# ITL230216.net
KiCad netlist of a schematic drawn in Altium Designer
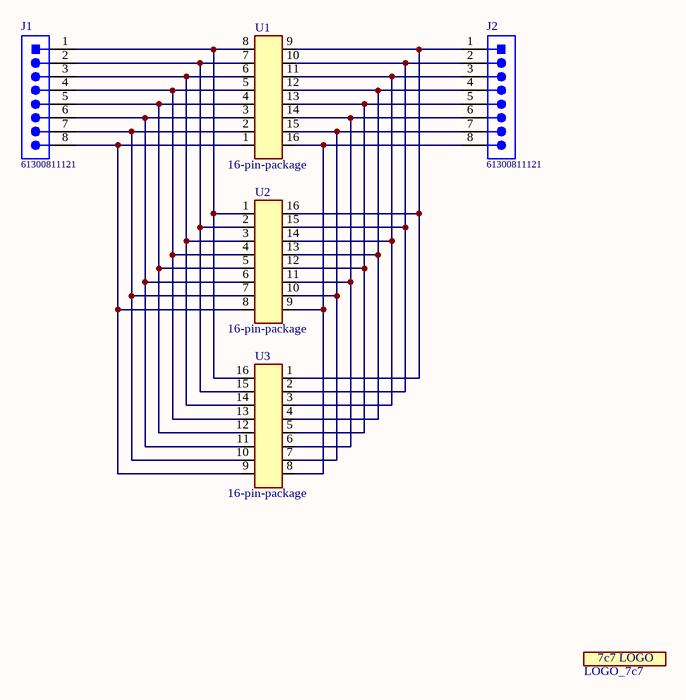
[diagram p0: ITL230216.SchDoc]

(export (version "E")
  (design (tool "Eeschema 10.0.6"))
  (components
    (comp (ref "GR1")
      (value "LOGO_7c7")
      (footprint "LOGO_7c7_silk_3MM")
      (description "The 7c7 logo: Be proud of our designs and stamp that logo on there!")
      (libsource (lib "7c7 Engineering") (part "LOGO_7c7-Symbol-1"))
    )
    (comp (ref "J1")
      (value "61300811121")
      (footprint "61300811121")
      (description "WR-PHD Pin Header, THT, pitch 2.54mm, Single Row, Vertical, 8p")
      (fields (field (name "MANUFACTURER") "Wurth Elektronik"))
      (libsource (lib "") (part "HDR8_1"))
    )
    (comp (ref "J2")
      (value "61300811121")
      (footprint "61300811121")
      (description "WR-PHD Pin Header, THT, pitch 2.54mm, Single Row, Vertical, 8p")
      (fields (field (name "MANUFACTURER") "Wurth Elektronik"))
      (libsource (lib "7c7 Engineering") (part "HDR8"))
    )
    (comp (ref "U1")
      (value "16-pin-package")
      (footprint "TSSOP16-0.65-4.4-L")
      (description "package adapter")
      (libsource (lib "7c7 Engineering") (part "16 pin device"))
    )
    (comp (ref "U2")
      (value "16-pin-package")
      (footprint "SOP16-N")
      (description "package adapter")
      (libsource (lib "") (part "16 pin device_1"))
    )
    (comp (ref "U3")
      (value "16-pin-package")
      (footprint "MSOP16")
      (description "package adapter")
      (libsource (lib "") (part "16 pin device_2"))
    )
  )
  (nets
    (net (code "1") (name "Net-(J1-Pad1)") (class "Default")
      (node (ref "J1") (pin "1") (pinfunction "1_1") (pintype "passive"))
      (node (ref "U1") (pin "8") (pinfunction "8_8") (pintype "power_in"))
      (node (ref "U2") (pin "1") (pinfunction "1_1") (pintype "power_in"))
      (node (ref "U3") (pin "16") (pinfunction "16_16") (pintype "power_in"))
    )
    (net (code "2") (name "Net-(J1-Pad2)") (class "Default")
      (node (ref "J1") (pin "2") (pinfunction "2_2") (pintype "passive"))
      (node (ref "U1") (pin "7") (pinfunction "7_7") (pintype "power_in"))
      (node (ref "U2") (pin "2") (pinfunction "2_2") (pintype "power_in"))
      (node (ref "U3") (pin "15") (pinfunction "15_15") (pintype "power_in"))
    )
    (net (code "3") (name "Net-(J1-Pad3)") (class "Default")
      (node (ref "J1") (pin "3") (pinfunction "3_3") (pintype "passive"))
      (node (ref "U1") (pin "6") (pinfunction "6_6") (pintype "power_in"))
      (node (ref "U2") (pin "3") (pinfunction "3_3") (pintype "power_in"))
      (node (ref "U3") (pin "14") (pinfunction "14_14") (pintype "power_in"))
    )
    (net (code "4") (name "Net-(J1-Pad4)") (class "Default")
      (node (ref "J1") (pin "4") (pinfunction "4_4") (pintype "passive"))
      (node (ref "U1") (pin "5") (pinfunction "5_5") (pintype "power_in"))
      (node (ref "U2") (pin "4") (pinfunction "4_4") (pintype "power_in"))
      (node (ref "U3") (pin "13") (pinfunction "13_13") (pintype "power_in"))
    )
    (net (code "5") (name "Net-(J1-Pad5)") (class "Default")
      (node (ref "J1") (pin "5") (pinfunction "5_5") (pintype "passive"))
      (node (ref "U1") (pin "4") (pinfunction "4_4") (pintype "power_in"))
      (node (ref "U2") (pin "5") (pinfunction "5_5") (pintype "power_in"))
      (node (ref "U3") (pin "12") (pinfunction "12_12") (pintype "power_in"))
    )
    (net (code "6") (name "Net-(J1-Pad6)") (class "Default")
      (node (ref "J1") (pin "6") (pinfunction "6_6") (pintype "passive"))
      (node (ref "U1") (pin "3") (pinfunction "3_3") (pintype "power_in"))
      (node (ref "U2") (pin "6") (pinfunction "6_6") (pintype "power_in"))
      (node (ref "U3") (pin "11") (pinfunction "11_11") (pintype "power_in"))
    )
    (net (code "7") (name "Net-(J1-Pad7)") (class "Default")
      (node (ref "J1") (pin "7") (pinfunction "7_7") (pintype "passive"))
      (node (ref "U1") (pin "2") (pinfunction "2_2") (pintype "power_in"))
      (node (ref "U2") (pin "7") (pinfunction "7_7") (pintype "power_in"))
      (node (ref "U3") (pin "10") (pinfunction "10_10") (pintype "power_in"))
    )
    (net (code "8") (name "Net-(J1-Pad8)") (class "Default")
      (node (ref "J1") (pin "8") (pinfunction "8_8") (pintype "passive"))
      (node (ref "U1") (pin "1") (pinfunction "1_1") (pintype "power_in"))
      (node (ref "U2") (pin "8") (pinfunction "8_8") (pintype "power_in"))
      (node (ref "U3") (pin "9") (pinfunction "9_9") (pintype "power_in"))
    )
    (net (code "9") (name "Net-(J2-Pad1)") (class "Default")
      (node (ref "J2") (pin "1") (pinfunction "1_1") (pintype "passive"))
      (node (ref "U1") (pin "9") (pinfunction "9_9") (pintype "power_in"))
      (node (ref "U2") (pin "16") (pinfunction "16_16") (pintype "power_in"))
      (node (ref "U3") (pin "1") (pinfunction "1_1") (pintype "power_in"))
    )
    (net (code "10") (name "Net-(J2-Pad2)") (class "Default")
      (node (ref "J2") (pin "2") (pinfunction "2_2") (pintype "passive"))
      (node (ref "U1") (pin "10") (pinfunction "10_10") (pintype "power_in"))
      (node (ref "U2") (pin "15") (pinfunction "15_15") (pintype "power_in"))
      (node (ref "U3") (pin "2") (pinfunction "2_2") (pintype "power_in"))
    )
    (net (code "11") (name "Net-(J2-Pad3)") (class "Default")
      (node (ref "J2") (pin "3") (pinfunction "3_3") (pintype "passive"))
      (node (ref "U1") (pin "11") (pinfunction "11_11") (pintype "power_in"))
      (node (ref "U2") (pin "14") (pinfunction "14_14") (pintype "power_in"))
      (node (ref "U3") (pin "3") (pinfunction "3_3") (pintype "power_in"))
    )
    (net (code "12") (name "Net-(J2-Pad4)") (class "Default")
      (node (ref "J2") (pin "4") (pinfunction "4_4") (pintype "passive"))
      (node (ref "U1") (pin "12") (pinfunction "12_12") (pintype "power_in"))
      (node (ref "U2") (pin "13") (pinfunction "13_13") (pintype "power_in"))
      (node (ref "U3") (pin "4") (pinfunction "4_4") (pintype "power_in"))
    )
    (net (code "13") (name "Net-(J2-Pad5)") (class "Default")
      (node (ref "J2") (pin "5") (pinfunction "5_5") (pintype "passive"))
      (node (ref "U1") (pin "13") (pinfunction "13_13") (pintype "power_in"))
      (node (ref "U2") (pin "12") (pinfunction "12_12") (pintype "power_in"))
      (node (ref "U3") (pin "5") (pinfunction "5_5") (pintype "power_in"))
    )
    (net (code "14") (name "Net-(J2-Pad6)") (class "Default")
      (node (ref "J2") (pin "6") (pinfunction "6_6") (pintype "passive"))
      (node (ref "U1") (pin "14") (pinfunction "14_14") (pintype "power_in"))
      (node (ref "U2") (pin "11") (pinfunction "11_11") (pintype "power_in"))
      (node (ref "U3") (pin "6") (pinfunction "6_6") (pintype "power_in"))
    )
    (net (code "15") (name "Net-(J2-Pad7)") (class "Default")
      (node (ref "J2") (pin "7") (pinfunction "7_7") (pintype "passive"))
      (node (ref "U1") (pin "15") (pinfunction "15_15") (pintype "power_in"))
      (node (ref "U2") (pin "10") (pinfunction "10_10") (pintype "power_in"))
      (node (ref "U3") (pin "7") (pinfunction "7_7") (pintype "power_in"))
    )
    (net (code "16") (name "Net-(J2-Pad8)") (class "Default")
      (node (ref "J2") (pin "8") (pinfunction "8_8") (pintype "passive"))
      (node (ref "U1") (pin "16") (pinfunction "16_16") (pintype "power_in"))
      (node (ref "U2") (pin "9") (pinfunction "9_9") (pintype "power_in"))
      (node (ref "U3") (pin "8") (pinfunction "8_8") (pintype "power_in"))
    )
  )
)
